# TCS37425_SCH.net
KiCad netlist of a schematic drawn in Altium Designer
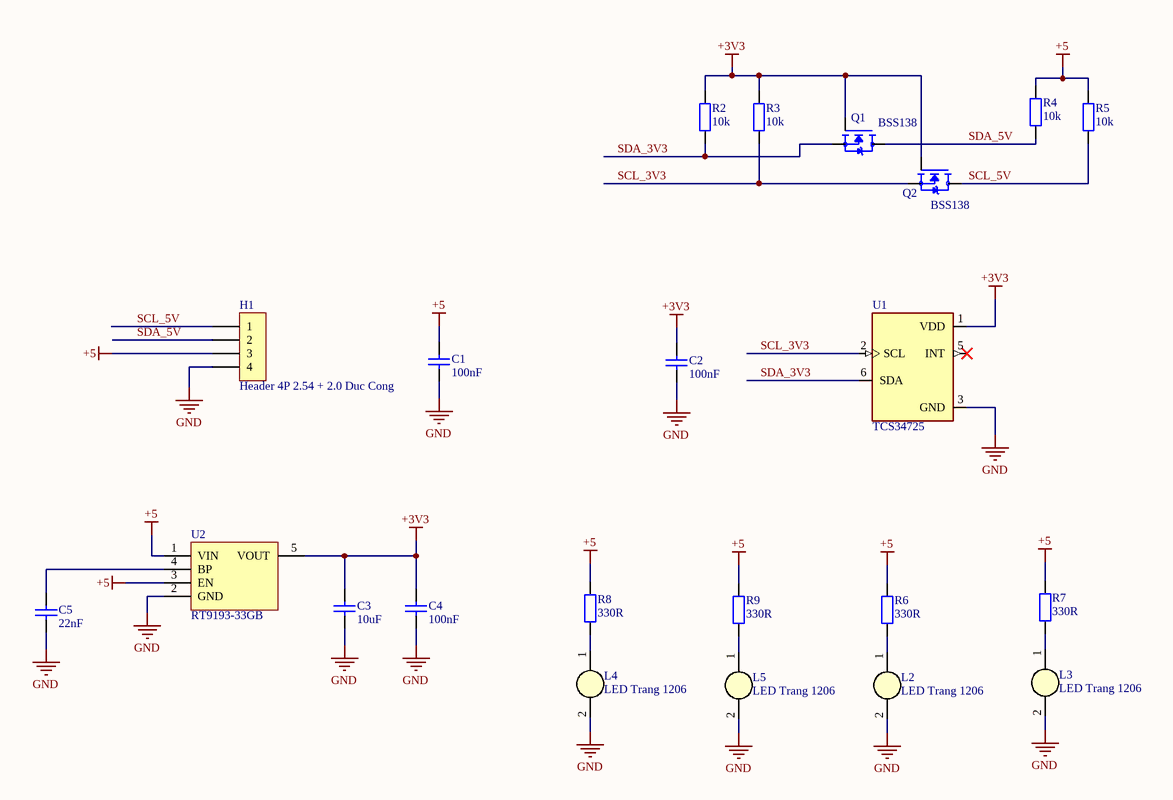
[diagram p0: TCS37425_SCH.SchDoc]

(export (version "E")
  (design (tool "Eeschema 10.0.6"))
  (components
    (comp (ref "C1")
      (value "100nF")
      (footprint "tu 0603")
      (description "Dán")
      (libsource (lib "namnt_Lib") (part "Tu 0603 104 50V 10%"))
    )
    (comp (ref "C2")
      (value "100nF")
      (footprint "tu 0603")
      (description "Dán")
      (libsource (lib "namnt_Lib") (part "Tu 0603 104 50V 10%"))
    )
    (comp (ref "C3")
      (value "10uF")
      (footprint "tu 0603")
      (description "Dán")
      (libsource (lib "namnt_Lib") (part "Tu 0603 106 16V 20%"))
    )
    (comp (ref "C4")
      (value "100nF")
      (footprint "tu 0603")
      (description "Dán")
      (libsource (lib "namnt_Lib") (part "Tu 0603 104 50V 10%"))
    )
    (comp (ref "C5")
      (value "22nF")
      (footprint "tu 0603")
      (description "Dán")
      (libsource (lib "namnt_Lib") (part "Tu 0603 104 50V 10%"))
    )
    (comp (ref "H1")
      (value "Header 4P 2.54 + 2.0 Duc Cong")
      (footprint "Header 4P DC 2.54 + 2.0")
      (description "Cắm")
      (libsource (lib "namnt_Lib") (part "Header 4P 2.54 + 2.0 Duc Cong"))
    )
    (comp (ref "L2")
      (value "LED Trang 1206")
      (footprint "LED-1206-Yellow")
      (description "Dán")
      (libsource (lib "namnt_Lib") (part "LED 1206 Trang"))
    )
    (comp (ref "L3")
      (value "LED Trang 1206")
      (footprint "LED-1206-Yellow")
      (description "Dán")
      (libsource (lib "namnt_Lib") (part "LED 1206 Trang"))
    )
    (comp (ref "L4")
      (value "LED Trang 1206")
      (footprint "LED-1206-Yellow")
      (description "Dán")
      (libsource (lib "namnt_Lib") (part "LED 1206 Trang"))
    )
    (comp (ref "L5")
      (value "LED Trang 1206")
      (footprint "LED-1206-Yellow")
      (description "Dán")
      (libsource (lib "namnt_Lib") (part "LED 1206 Trang"))
    )
    (comp (ref "Q1")
      (value "BSS138")
      (footprint "SOT95P240X111-3N")
      (description "N-Channel 50 V 220mA (Ta) 350mW (Ta) Surface Mount SOT-23-3")
      (fields (field (name "MF") "onsemi"))
      (libsource (lib "namnt_Lib") (part "BSS138"))
    )
    (comp (ref "Q2")
      (value "BSS138")
      (footprint "SOT95P240X111-3N")
      (description "N-Channel 50 V 220mA (Ta) 350mW (Ta) Surface Mount SOT-23-3")
      (fields (field (name "MF") "onsemi"))
      (libsource (lib "namnt_Lib") (part "BSS138"))
    )
    (comp (ref "R2")
      (value "10k")
      (footprint "tro smd 0603")
      (description "Dán")
      (libsource (lib "namnt_Lib") (part "Tro 0603 1% 10k"))
    )
    (comp (ref "R3")
      (value "10k")
      (footprint "tro smd 0603")
      (description "Dán")
      (libsource (lib "namnt_Lib") (part "Tro 0603 1% 10k"))
    )
    (comp (ref "R4")
      (value "10k")
      (footprint "tro smd 0603")
      (description "Dán")
      (libsource (lib "namnt_Lib") (part "Tro 0603 1% 10k"))
    )
    (comp (ref "R5")
      (value "10k")
      (footprint "tro smd 0603")
      (description "Dán")
      (libsource (lib "namnt_Lib") (part "Tro 0603 1% 10k"))
    )
    (comp (ref "R6")
      (value "330R")
      (footprint "tro smd 0603")
      (description "Dán")
      (libsource (lib "namnt_Lib") (part "Tro 0603 5% 330R"))
    )
    (comp (ref "R7")
      (value "330R")
      (footprint "tro smd 0603")
      (description "Dán")
      (libsource (lib "namnt_Lib") (part "Tro 0603 5% 330R"))
    )
    (comp (ref "R8")
      (value "330R")
      (footprint "tro smd 0603")
      (description "Dán")
      (libsource (lib "namnt_Lib") (part "Tro 0603 5% 330R"))
    )
    (comp (ref "R9")
      (value "330R")
      (footprint "tro smd 0603")
      (description "Dán")
      (libsource (lib "namnt_Lib") (part "Tro 0603 5% 330R"))
    )
    (comp (ref "U1")
      (value "TCS34725")
      (footprint "SON65P200X240X70-6N")
      (fields (field (name "MP") "TCS34725FN") (field (name "MF") "ams"))
      (libsource (lib "namnt_Lib") (part "TCS34725"))
    )
    (comp (ref "U2")
      (value "RT9193-33GB")
      (footprint "SOT23-5")
      (description "Linear Voltage Regulator IC 1 Output 300mA SOT-23-5")
      (fields (field (name "MANUFACTURER") "Richtek USA Inc."))
      (libsource (lib "namnt_Lib") (part "REG_5.5V-3.3V-0.3A-1W-SOT-23-5"))
    )
  )
  (nets
    (net (code "1") (name "+3V3") (class "Default")
      (node (ref "C2") (pin "1") (pinfunction "1_1") (pintype "passive"))
      (node (ref "C3") (pin "1") (pinfunction "1_1") (pintype "passive"))
      (node (ref "C4") (pin "1") (pinfunction "1_1") (pintype "passive"))
      (node (ref "Q1") (pin "1") (pinfunction "G_1") (pintype "passive"))
      (node (ref "Q2") (pin "1") (pinfunction "G_1") (pintype "passive"))
      (node (ref "R2") (pin "2") (pinfunction "2_2") (pintype "passive"))
      (node (ref "R3") (pin "2") (pinfunction "2_2") (pintype "passive"))
      (node (ref "U1") (pin "1") (pinfunction "VDD_1") (pintype "power_in"))
      (node (ref "U2") (pin "5") (pinfunction "VOUT_5") (pintype "passive"))
    )
    (net (code "2") (name "+5") (class "Default")
      (node (ref "C1") (pin "1") (pinfunction "1_1") (pintype "passive"))
      (node (ref "H1") (pin "3") (pinfunction "3_3") (pintype "passive"))
      (node (ref "R4") (pin "2") (pinfunction "2_2") (pintype "passive"))
      (node (ref "R5") (pin "2") (pinfunction "2_2") (pintype "passive"))
      (node (ref "R6") (pin "2") (pinfunction "2_2") (pintype "passive"))
      (node (ref "R7") (pin "2") (pinfunction "2_2") (pintype "passive"))
      (node (ref "R8") (pin "2") (pinfunction "2_2") (pintype "passive"))
      (node (ref "R9") (pin "2") (pinfunction "2_2") (pintype "passive"))
      (node (ref "U2") (pin "1") (pinfunction "VIN_1") (pintype "passive"))
      (node (ref "U2") (pin "3") (pinfunction "EN_3") (pintype "passive"))
    )
    (net (code "3") (name "/SCL_3V3") (class "Default")
      (node (ref "Q2") (pin "2") (pinfunction "S_2") (pintype "passive"))
      (node (ref "R3") (pin "1") (pinfunction "1_1") (pintype "passive"))
      (node (ref "U1") (pin "2") (pinfunction "SCL_2") (pintype "input"))
    )
    (net (code "4") (name "/SCL_5V") (class "Default")
      (node (ref "H1") (pin "1") (pinfunction "1_1") (pintype "passive"))
      (node (ref "Q2") (pin "3") (pinfunction "D_3") (pintype "passive"))
      (node (ref "R5") (pin "1") (pinfunction "1_1") (pintype "passive"))
    )
    (net (code "5") (name "/SDA_3V3") (class "Default")
      (node (ref "Q1") (pin "2") (pinfunction "S_2") (pintype "passive"))
      (node (ref "R2") (pin "1") (pinfunction "1_1") (pintype "passive"))
      (node (ref "U1") (pin "6") (pinfunction "SDA_6") (pintype "bidirectional"))
    )
    (net (code "6") (name "/SDA_5V") (class "Default")
      (node (ref "H1") (pin "2") (pinfunction "2_2") (pintype "passive"))
      (node (ref "Q1") (pin "3") (pinfunction "D_3") (pintype "passive"))
      (node (ref "R4") (pin "1") (pinfunction "1_1") (pintype "passive"))
    )
    (net (code "7") (name "GND") (class "Default")
      (node (ref "C1") (pin "2") (pinfunction "2_2") (pintype "passive"))
      (node (ref "C2") (pin "2") (pinfunction "2_2") (pintype "passive"))
      (node (ref "C3") (pin "2") (pinfunction "2_2") (pintype "passive"))
      (node (ref "C4") (pin "2") (pinfunction "2_2") (pintype "passive"))
      (node (ref "C5") (pin "2") (pinfunction "2_2") (pintype "passive"))
      (node (ref "H1") (pin "4") (pinfunction "4_4") (pintype "passive"))
      (node (ref "L2") (pin "2") (pinfunction "K_2") (pintype "passive"))
      (node (ref "L3") (pin "2") (pinfunction "K_2") (pintype "passive"))
      (node (ref "L4") (pin "2") (pinfunction "K_2") (pintype "passive"))
      (node (ref "L5") (pin "2") (pinfunction "K_2") (pintype "passive"))
      (node (ref "U1") (pin "3") (pinfunction "GND_3") (pintype "power_in"))
      (node (ref "U2") (pin "2") (pinfunction "GND_2") (pintype "passive"))
    )
    (net (code "8") (name "Net-(L2-A)") (class "Default")
      (node (ref "L2") (pin "1") (pinfunction "A_1") (pintype "passive"))
      (node (ref "R6") (pin "1") (pinfunction "1_1") (pintype "passive"))
    )
    (net (code "9") (name "Net-(L3-A)") (class "Default")
      (node (ref "L3") (pin "1") (pinfunction "A_1") (pintype "passive"))
      (node (ref "R7") (pin "1") (pinfunction "1_1") (pintype "passive"))
    )
    (net (code "10") (name "Net-(L4-A)") (class "Default")
      (node (ref "L4") (pin "1") (pinfunction "A_1") (pintype "passive"))
      (node (ref "R8") (pin "1") (pinfunction "1_1") (pintype "passive"))
    )
    (net (code "11") (name "Net-(L5-A)") (class "Default")
      (node (ref "L5") (pin "1") (pinfunction "A_1") (pintype "passive"))
      (node (ref "R9") (pin "1") (pinfunction "1_1") (pintype "passive"))
    )
    (net (code "12") (name "Net-(U2-BP)") (class "Default")
      (node (ref "C5") (pin "1") (pinfunction "1_1") (pintype "passive"))
      (node (ref "U2") (pin "4") (pinfunction "BP_4") (pintype "passive"))
    )
    (net (code "13") (name "unconnected-(U1-INT-Pad5)") (class "Default")
      (node (ref "U1") (pin "5") (pinfunction "INT_5") (pintype "output+no_connect"))
    )
  )
)
